# Nucleo.net
KiCad netlist of a schematic drawn in Altium Designer
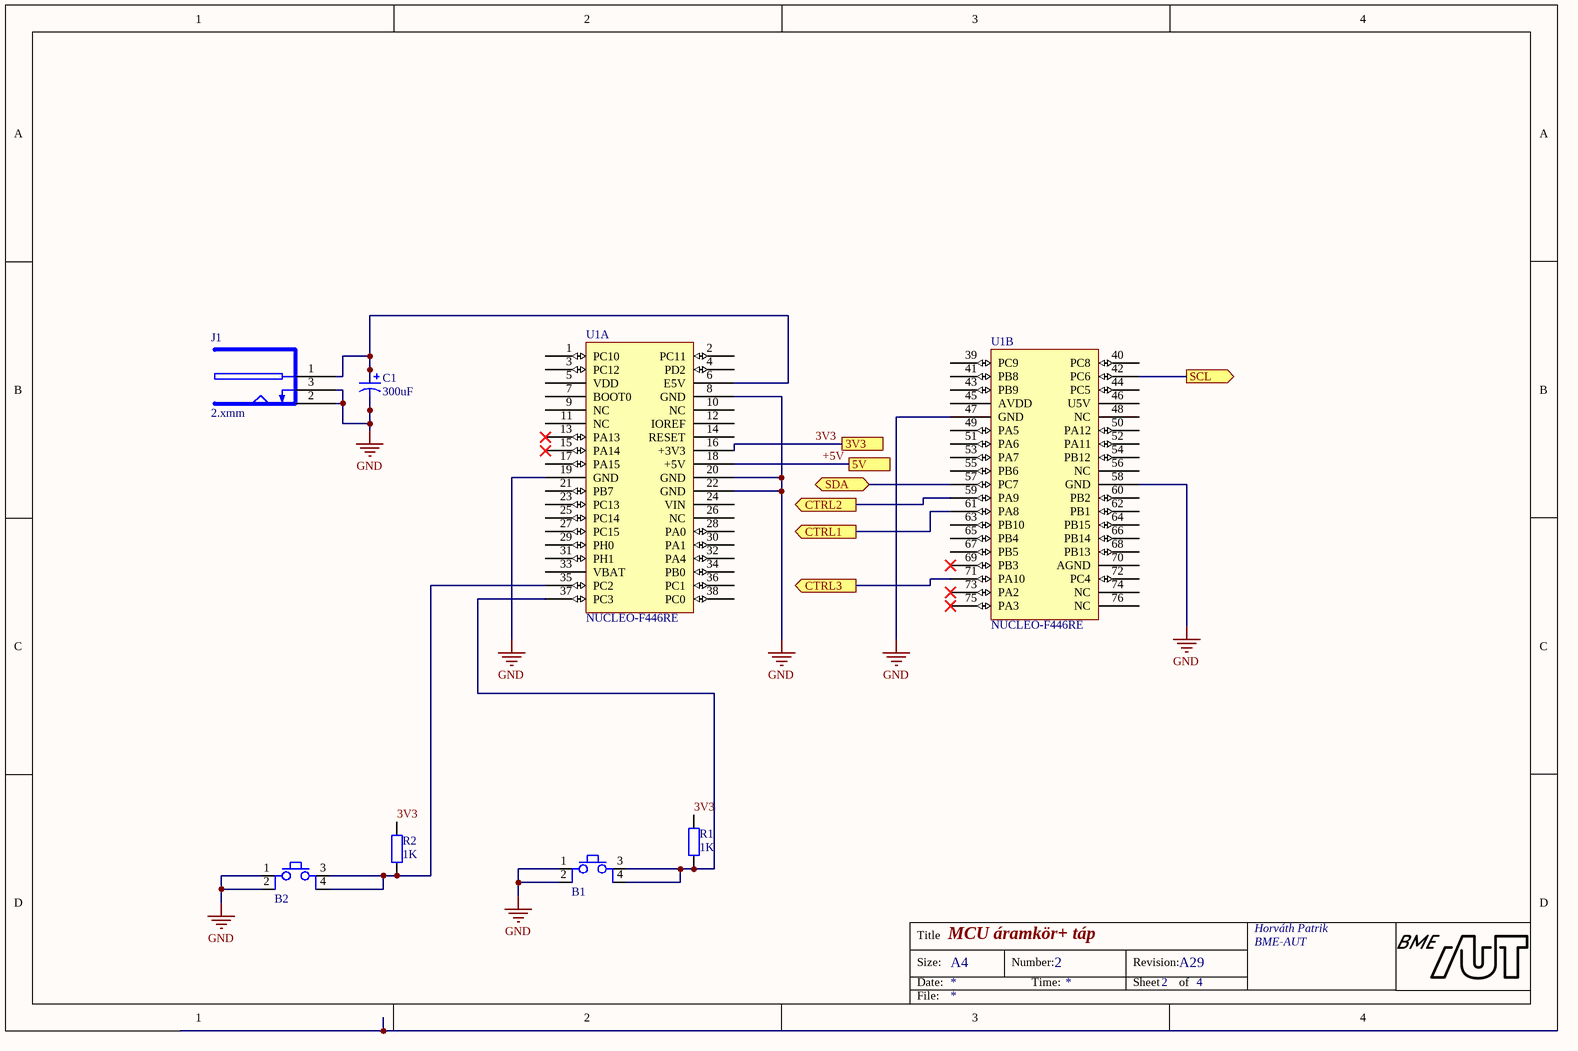
[diagram p0: Nucleo.SchDoc]

(export (version "E")
  (design (tool "Eeschema 10.0.6"))
  (components
    (comp (ref "B1")
      (value "Button")
      (footprint "FP_BTN_SMD")
      (description "Push button")
      (libsource (lib "hallglib") (part "Button 4P"))
    )
    (comp (ref "B2")
      (value "Button")
      (footprint "FP_BTN_SMD")
      (description "Push button")
      (libsource (lib "hallglib") (part "Button 4P"))
    )
    (comp (ref "C1")
      (value "300uF")
      (footprint "CAP_AE_8x10")
      (description "Polarized Capacitor")
      (fields (field (name "Comment") "100nF"))
      (libsource (lib "hallglib") (part "CAP_ELECT"))
    )
    (comp (ref "J1")
      (value "2.xmm")
      (footprint "FP_DC_TAP_ANYA")
      (description "2.xmm DC HEBA25 TÁPFESZÜLTSÉG ALJZAT ZÁRT, NYÁKBA 90°")
      (libsource (lib "hallglib") (part "DC_TAP_ANYA"))
    )
    (comp (ref "R1")
      (value "1K")
      (footprint "FP_0805_RES")
      (description "Resistor")
      (libsource (lib "hallglib") (part "RES"))
    )
    (comp (ref "R2")
      (value "1K")
      (footprint "FP_0805_RES")
      (description "Resistor")
      (libsource (lib "hallglib") (part "RES"))
    )
    (comp (ref "U1")
      (value "NUCLEO-F446RE")
      (footprint "FP_NUCLEO-64")
      (libsource (lib "hallglib") (part "NUCLEO-F446RE"))
    )
  )
  (nets
    (net (code "1") (name "/+5V") (class "Default")
      (node (ref "U1") (pin "18") (pinfunction "+5V_18") (pintype "power_in"))
    )
    (net (code "2") (name "/3V3") (class "Default")
      (node (ref "R1") (pin "2") (pinfunction "2_2") (pintype "passive"))
      (node (ref "R2") (pin "2") (pinfunction "2_2") (pintype "passive"))
      (node (ref "U1") (pin "16") (pinfunction "+3V3_16") (pintype "power_in"))
    )
    (net (code "3") (name "/CTRL1") (class "Default")
      (node (ref "U1") (pin "61") (pinfunction "PA8_61") (pintype "bidirectional"))
    )
    (net (code "4") (name "/CTRL2") (class "Default")
      (node (ref "U1") (pin "59") (pinfunction "PA9_59") (pintype "bidirectional"))
    )
    (net (code "5") (name "/CTRL3") (class "Default")
      (node (ref "U1") (pin "71") (pinfunction "PA10_71") (pintype "bidirectional"))
    )
    (net (code "6") (name "/SCL") (class "Default")
      (node (ref "U1") (pin "42") (pinfunction "PC6_42") (pintype "bidirectional"))
    )
    (net (code "7") (name "/SDA") (class "Default")
      (node (ref "U1") (pin "57") (pinfunction "PC7_57") (pintype "bidirectional"))
    )
    (net (code "8") (name "GND") (class "Default")
      (node (ref "B1") (pin "1") (pinfunction "1_1") (pintype "passive"))
      (node (ref "B1") (pin "2") (pinfunction "2_2") (pintype "passive"))
      (node (ref "B2") (pin "1") (pinfunction "1_1") (pintype "passive"))
      (node (ref "B2") (pin "2") (pinfunction "2_2") (pintype "passive"))
      (node (ref "C1") (pin "1") (pinfunction "1_1") (pintype "power_in"))
      (node (ref "J1") (pin "2") (pinfunction "SLEEVE_2") (pintype "power_in"))
      (node (ref "J1") (pin "3") (pinfunction "BREAK_3") (pintype "power_in"))
      (node (ref "U1") (pin "19") (pinfunction "GND_19") (pintype "passive"))
      (node (ref "U1") (pin "20") (pinfunction "GND_20") (pintype "passive"))
      (node (ref "U1") (pin "22") (pinfunction "GND_22") (pintype "passive"))
      (node (ref "U1") (pin "47") (pinfunction "GND_47") (pintype "passive"))
      (node (ref "U1") (pin "58") (pinfunction "GND_58") (pintype "passive"))
      (node (ref "U1") (pin "8") (pinfunction "GND_8") (pintype "passive"))
    )
    (net (code "9") (name "Net-(J1-PIN)") (class "Default")
      (node (ref "C1") (pin "2") (pinfunction "2_2") (pintype "power_in"))
      (node (ref "J1") (pin "1") (pinfunction "PIN_1") (pintype "power_in"))
      (node (ref "U1") (pin "6") (pinfunction "E5V_6") (pintype "power_in"))
    )
    (net (code "10") (name "Net-(U1A-PC2)") (class "Default")
      (node (ref "B2") (pin "3") (pinfunction "3_3") (pintype "passive"))
      (node (ref "B2") (pin "4") (pinfunction "4_4") (pintype "passive"))
      (node (ref "R2") (pin "1") (pinfunction "1_1") (pintype "passive"))
      (node (ref "U1") (pin "35") (pinfunction "PC2_35") (pintype "bidirectional"))
    )
    (net (code "11") (name "Net-(U1A-PC3)") (class "Default")
      (node (ref "B1") (pin "3") (pinfunction "3_3") (pintype "passive"))
      (node (ref "B1") (pin "4") (pinfunction "4_4") (pintype "passive"))
      (node (ref "R1") (pin "1") (pinfunction "1_1") (pintype "passive"))
      (node (ref "U1") (pin "37") (pinfunction "PC3_37") (pintype "bidirectional"))
    )
    (net (code "12") (name "unconnected-(U1A-BOOT0-Pad7)") (class "Default")
      (node (ref "U1") (pin "7") (pinfunction "BOOT0_7") (pintype "passive"))
    )
    (net (code "13") (name "unconnected-(U1A-IOREF-Pad12)") (class "Default")
      (node (ref "U1") (pin "12") (pinfunction "IOREF_12") (pintype "passive"))
    )
    (net (code "14") (name "unconnected-(U1A-NC-Pad9)") (class "Default")
      (node (ref "U1") (pin "9") (pinfunction "NC_9") (pintype "passive"))
    )
    (net (code "15") (name "unconnected-(U1A-NC-Pad10)") (class "Default")
      (node (ref "U1") (pin "10") (pinfunction "NC_10") (pintype "passive"))
    )
    (net (code "16") (name "unconnected-(U1A-NC-Pad11)") (class "Default")
      (node (ref "U1") (pin "11") (pinfunction "NC_11") (pintype "passive"))
    )
    (net (code "17") (name "unconnected-(U1A-NC-Pad26)") (class "Default")
      (node (ref "U1") (pin "26") (pinfunction "NC_26") (pintype "passive"))
    )
    (net (code "18") (name "unconnected-(U1A-PA0-Pad28)") (class "Default")
      (node (ref "U1") (pin "28") (pinfunction "PA0_28") (pintype "bidirectional"))
    )
    (net (code "19") (name "unconnected-(U1A-PA1-Pad30)") (class "Default")
      (node (ref "U1") (pin "30") (pinfunction "PA1_30") (pintype "bidirectional"))
    )
    (net (code "20") (name "unconnected-(U1A-PA4-Pad32)") (class "Default")
      (node (ref "U1") (pin "32") (pinfunction "PA4_32") (pintype "bidirectional"))
    )
    (net (code "21") (name "unconnected-(U1A-PA13-Pad13)") (class "Default")
      (node (ref "U1") (pin "13") (pinfunction "PA13_13") (pintype "bidirectional+no_connect"))
    )
    (net (code "22") (name "unconnected-(U1A-PA14-Pad15)") (class "Default")
      (node (ref "U1") (pin "15") (pinfunction "PA14_15") (pintype "bidirectional+no_connect"))
    )
    (net (code "23") (name "unconnected-(U1A-PA15-Pad17)") (class "Default")
      (node (ref "U1") (pin "17") (pinfunction "PA15_17") (pintype "bidirectional"))
    )
    (net (code "24") (name "unconnected-(U1A-PB0-Pad34)") (class "Default")
      (node (ref "U1") (pin "34") (pinfunction "PB0_34") (pintype "bidirectional"))
    )
    (net (code "25") (name "unconnected-(U1A-PB7-Pad21)") (class "Default")
      (node (ref "U1") (pin "21") (pinfunction "PB7_21") (pintype "bidirectional"))
    )
    (net (code "26") (name "unconnected-(U1A-PC0-Pad38)") (class "Default")
      (node (ref "U1") (pin "38") (pinfunction "PC0_38") (pintype "bidirectional"))
    )
    (net (code "27") (name "unconnected-(U1A-PC1-Pad36)") (class "Default")
      (node (ref "U1") (pin "36") (pinfunction "PC1_36") (pintype "bidirectional"))
    )
    (net (code "28") (name "unconnected-(U1A-PC10-Pad1)") (class "Default")
      (node (ref "U1") (pin "1") (pinfunction "PC10_1") (pintype "bidirectional"))
    )
    (net (code "29") (name "unconnected-(U1A-PC11-Pad2)") (class "Default")
      (node (ref "U1") (pin "2") (pinfunction "PC11_2") (pintype "bidirectional"))
    )
    (net (code "30") (name "unconnected-(U1A-PC12-Pad3)") (class "Default")
      (node (ref "U1") (pin "3") (pinfunction "PC12_3") (pintype "bidirectional"))
    )
    (net (code "31") (name "unconnected-(U1A-PC13-Pad23)") (class "Default")
      (node (ref "U1") (pin "23") (pinfunction "PC13_23") (pintype "bidirectional"))
    )
    (net (code "32") (name "unconnected-(U1A-PC14-Pad25)") (class "Default")
      (node (ref "U1") (pin "25") (pinfunction "PC14_25") (pintype "bidirectional"))
    )
    (net (code "33") (name "unconnected-(U1A-PC15-Pad27)") (class "Default")
      (node (ref "U1") (pin "27") (pinfunction "PC15_27") (pintype "bidirectional"))
    )
    (net (code "34") (name "unconnected-(U1A-PD2-Pad4)") (class "Default")
      (node (ref "U1") (pin "4") (pinfunction "PD2_4") (pintype "bidirectional"))
    )
    (net (code "35") (name "unconnected-(U1A-PH0-Pad29)") (class "Default")
      (node (ref "U1") (pin "29") (pinfunction "PH0_29") (pintype "bidirectional"))
    )
    (net (code "36") (name "unconnected-(U1A-PH1-Pad31)") (class "Default")
      (node (ref "U1") (pin "31") (pinfunction "PH1_31") (pintype "bidirectional"))
    )
    (net (code "37") (name "unconnected-(U1A-RESET-Pad14)") (class "Default")
      (node (ref "U1") (pin "14") (pinfunction "RESET_14") (pintype "passive"))
    )
    (net (code "38") (name "unconnected-(U1A-VBAT-Pad33)") (class "Default")
      (node (ref "U1") (pin "33") (pinfunction "VBAT_33") (pintype "power_in"))
    )
    (net (code "39") (name "unconnected-(U1A-VDD-Pad5)") (class "Default")
      (node (ref "U1") (pin "5") (pinfunction "VDD_5") (pintype "power_in"))
    )
    (net (code "40") (name "unconnected-(U1A-VIN-Pad24)") (class "Default")
      (node (ref "U1") (pin "24") (pinfunction "VIN_24") (pintype "power_in"))
    )
    (net (code "41") (name "unconnected-(U1B-AGND-Pad70)") (class "Default")
      (node (ref "U1") (pin "70") (pinfunction "AGND_70") (pintype "passive"))
    )
    (net (code "42") (name "unconnected-(U1B-AVDD-Pad45)") (class "Default")
      (node (ref "U1") (pin "45") (pinfunction "AVDD_45") (pintype "power_in"))
    )
    (net (code "43") (name "unconnected-(U1B-NC-Pad48)") (class "Default")
      (node (ref "U1") (pin "48") (pinfunction "NC_48") (pintype "passive"))
    )
    (net (code "44") (name "unconnected-(U1B-NC-Pad56)") (class "Default")
      (node (ref "U1") (pin "56") (pinfunction "NC_56") (pintype "passive"))
    )
    (net (code "45") (name "unconnected-(U1B-NC-Pad74)") (class "Default")
      (node (ref "U1") (pin "74") (pinfunction "NC_74") (pintype "passive"))
    )
    (net (code "46") (name "unconnected-(U1B-NC-Pad76)") (class "Default")
      (node (ref "U1") (pin "76") (pinfunction "NC_76") (pintype "passive"))
    )
    (net (code "47") (name "unconnected-(U1B-PA2-Pad73)") (class "Default")
      (node (ref "U1") (pin "73") (pinfunction "PA2_73") (pintype "bidirectional+no_connect"))
    )
    (net (code "48") (name "unconnected-(U1B-PA3-Pad75)") (class "Default")
      (node (ref "U1") (pin "75") (pinfunction "PA3_75") (pintype "bidirectional+no_connect"))
    )
    (net (code "49") (name "unconnected-(U1B-PA5-Pad49)") (class "Default")
      (node (ref "U1") (pin "49") (pinfunction "PA5_49") (pintype "bidirectional"))
    )
    (net (code "50") (name "unconnected-(U1B-PA6-Pad51)") (class "Default")
      (node (ref "U1") (pin "51") (pinfunction "PA6_51") (pintype "bidirectional"))
    )
    (net (code "51") (name "unconnected-(U1B-PA7-Pad53)") (class "Default")
      (node (ref "U1") (pin "53") (pinfunction "PA7_53") (pintype "bidirectional"))
    )
    (net (code "52") (name "unconnected-(U1B-PA11-Pad52)") (class "Default")
      (node (ref "U1") (pin "52") (pinfunction "PA11_52") (pintype "bidirectional"))
    )
    (net (code "53") (name "unconnected-(U1B-PA12-Pad50)") (class "Default")
      (node (ref "U1") (pin "50") (pinfunction "PA12_50") (pintype "bidirectional"))
    )
    (net (code "54") (name "unconnected-(U1B-PB1-Pad62)") (class "Default")
      (node (ref "U1") (pin "62") (pinfunction "PB1_62") (pintype "bidirectional"))
    )
    (net (code "55") (name "unconnected-(U1B-PB2-Pad60)") (class "Default")
      (node (ref "U1") (pin "60") (pinfunction "PB2_60") (pintype "bidirectional"))
    )
    (net (code "56") (name "unconnected-(U1B-PB3-Pad69)") (class "Default")
      (node (ref "U1") (pin "69") (pinfunction "PB3_69") (pintype "bidirectional+no_connect"))
    )
    (net (code "57") (name "unconnected-(U1B-PB4-Pad65)") (class "Default")
      (node (ref "U1") (pin "65") (pinfunction "PB4_65") (pintype "bidirectional"))
    )
    (net (code "58") (name "unconnected-(U1B-PB5-Pad67)") (class "Default")
      (node (ref "U1") (pin "67") (pinfunction "PB5_67") (pintype "bidirectional"))
    )
    (net (code "59") (name "unconnected-(U1B-PB6-Pad55)") (class "Default")
      (node (ref "U1") (pin "55") (pinfunction "PB6_55") (pintype "bidirectional"))
    )
    (net (code "60") (name "unconnected-(U1B-PB8-Pad41)") (class "Default")
      (node (ref "U1") (pin "41") (pinfunction "PB8_41") (pintype "bidirectional"))
    )
    (net (code "61") (name "unconnected-(U1B-PB9-Pad43)") (class "Default")
      (node (ref "U1") (pin "43") (pinfunction "PB9_43") (pintype "bidirectional"))
    )
    (net (code "62") (name "unconnected-(U1B-PB10-Pad63)") (class "Default")
      (node (ref "U1") (pin "63") (pinfunction "PB10_63") (pintype "bidirectional"))
    )
    (net (code "63") (name "unconnected-(U1B-PB12-Pad54)") (class "Default")
      (node (ref "U1") (pin "54") (pinfunction "PB12_54") (pintype "bidirectional"))
    )
    (net (code "64") (name "unconnected-(U1B-PB13-Pad68)") (class "Default")
      (node (ref "U1") (pin "68") (pinfunction "PB13_68") (pintype "bidirectional"))
    )
    (net (code "65") (name "unconnected-(U1B-PB14-Pad66)") (class "Default")
      (node (ref "U1") (pin "66") (pinfunction "PB14_66") (pintype "bidirectional"))
    )
    (net (code "66") (name "unconnected-(U1B-PB15-Pad64)") (class "Default")
      (node (ref "U1") (pin "64") (pinfunction "PB15_64") (pintype "bidirectional"))
    )
    (net (code "67") (name "unconnected-(U1B-PC4-Pad72)") (class "Default")
      (node (ref "U1") (pin "72") (pinfunction "PC4_72") (pintype "bidirectional"))
    )
    (net (code "68") (name "unconnected-(U1B-PC5-Pad44)") (class "Default")
      (node (ref "U1") (pin "44") (pinfunction "PC5_44") (pintype "bidirectional"))
    )
    (net (code "69") (name "unconnected-(U1B-PC8-Pad40)") (class "Default")
      (node (ref "U1") (pin "40") (pinfunction "PC8_40") (pintype "bidirectional"))
    )
    (net (code "70") (name "unconnected-(U1B-PC9-Pad39)") (class "Default")
      (node (ref "U1") (pin "39") (pinfunction "PC9_39") (pintype "bidirectional"))
    )
    (net (code "71") (name "unconnected-(U1B-U5V-Pad46)") (class "Default")
      (node (ref "U1") (pin "46") (pinfunction "U5V_46") (pintype "power_in"))
    )
  )
)
